# CO2_Sensor_SCD40.net
KiCad netlist of a schematic drawn in EAGLE
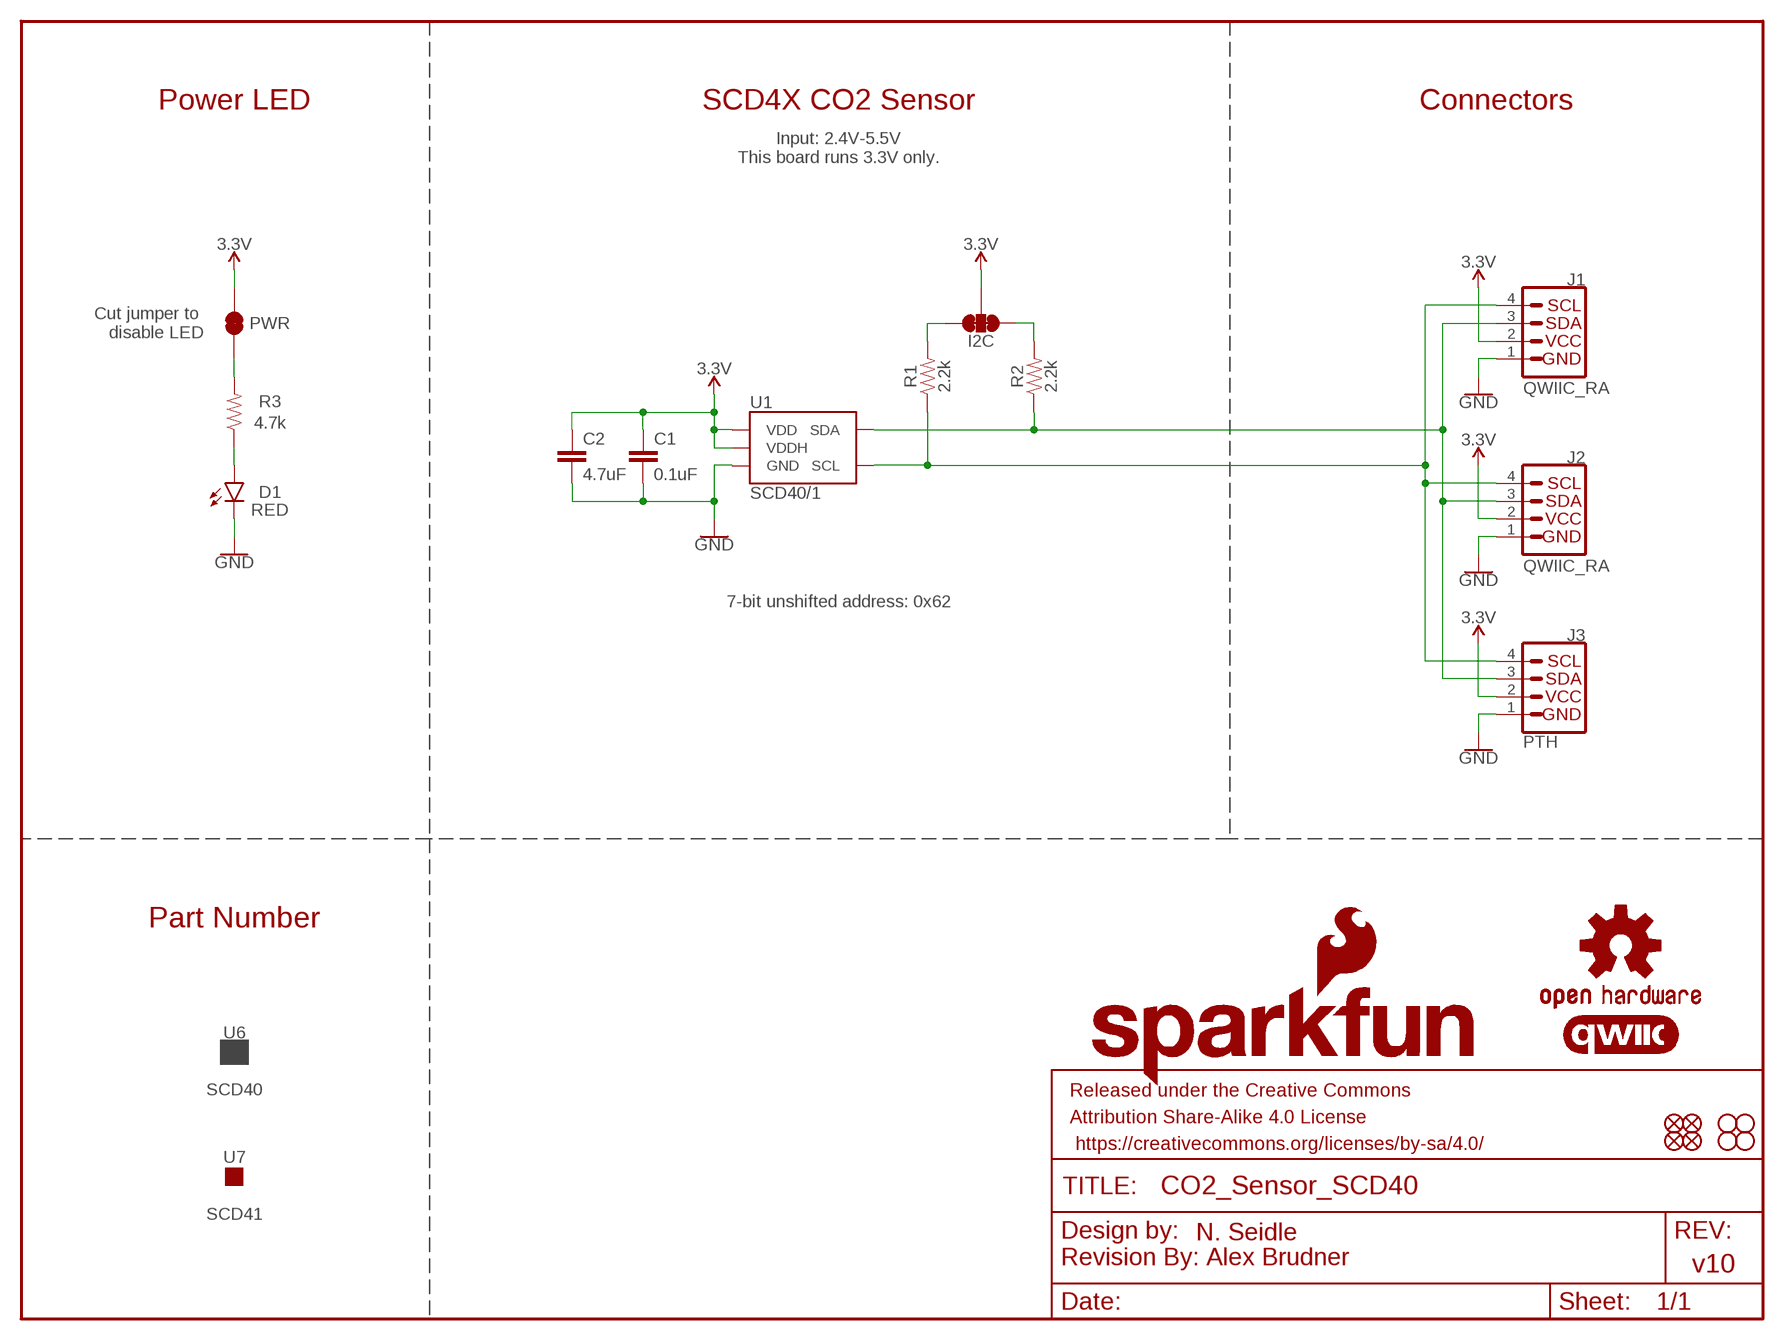
[diagram p0: schematic, sheet 1]

(export (version "E")
  (design (tool "Eeschema 10.0.6"))
  (components
    (comp (ref "C1")
      (value "0.1uF")
      (footprint "eagle-import:0603")
      (libsource (lib "eagle-import") (part "0.1UF-0603-25V-10%-X7R-WE"))
    )
    (comp (ref "C2")
      (value "4.7uF")
      (footprint "eagle-import:0603")
      (libsource (lib "eagle-import") (part "4.7UF-0603-6.3V-(10%)"))
    )
    (comp (ref "D1")
      (value "RED")
      (footprint "eagle-import:LED-0603")
      (libsource (lib "eagle-import") (part "LED-RED_0603-KB"))
    )
    (comp (ref "FD1")
      (value "FIDUCIALUFIDUCIAL")
      (footprint "eagle-import:FIDUCIAL-MICRO")
      (libsource (lib "eagle-import") (part "FIDUCIALUFIDUCIAL"))
    )
    (comp (ref "FD2")
      (value "FIDUCIALUFIDUCIAL")
      (footprint "eagle-import:FIDUCIAL-MICRO")
      (libsource (lib "eagle-import") (part "FIDUCIALUFIDUCIAL"))
    )
    (comp (ref "FD3")
      (value "FIDUCIALUFIDUCIAL")
      (footprint "eagle-import:FIDUCIAL-MICRO")
      (libsource (lib "eagle-import") (part "FIDUCIALUFIDUCIAL"))
    )
    (comp (ref "FD4")
      (value "FIDUCIALUFIDUCIAL")
      (footprint "eagle-import:FIDUCIAL-MICRO")
      (libsource (lib "eagle-import") (part "FIDUCIALUFIDUCIAL"))
    )
    (comp (ref "FRAME1")
      (value "FRAME-LETTER")
      (footprint "eagle-import:CREATIVE_COMMONS")
      (fields
        (field (name "BASEDON") "Revision By: Alex Brudner")
        (field (name "DESIGNER") "N. Seidle")
        (field (name "REV") "v10")
      )
      (libsource (lib "eagle-import") (part "FRAME-LETTER"))
    )
    (comp (ref "H1")
      (value "STAND-OFF")
      (footprint "eagle-import:STAND-OFF")
      (libsource (lib "eagle-import") (part "STAND-OFF"))
    )
    (comp (ref "H2")
      (value "STAND-OFF")
      (footprint "eagle-import:STAND-OFF")
      (libsource (lib "eagle-import") (part "STAND-OFF"))
    )
    (comp (ref "H3")
      (value "STAND-OFF")
      (footprint "eagle-import:STAND-OFF")
      (libsource (lib "eagle-import") (part "STAND-OFF"))
    )
    (comp (ref "H4")
      (value "STAND-OFF")
      (footprint "eagle-import:STAND-OFF")
      (libsource (lib "eagle-import") (part "STAND-OFF"))
    )
    (comp (ref "I2C")
      (value "I2C")
      (footprint "eagle-import:SMT-JUMPER_3_2-NC_TRACE_SILK")
      (libsource (lib "eagle-import") (part "JUMPER-SMT_3_2-NC_TRACE_SILK"))
    )
    (comp (ref "J1")
      (value "QWIIC_RA")
      (footprint "eagle-import:JST04_1MM_RA")
      (libsource (lib "eagle-import") (part "QWIIC_CONNECTORJS-1MM"))
    )
    (comp (ref "J2")
      (value "QWIIC_RA")
      (footprint "eagle-import:JST04_1MM_RA")
      (libsource (lib "eagle-import") (part "QWIIC_CONNECTORJS-1MM"))
    )
    (comp (ref "J3")
      (value "PTH")
      (footprint "eagle-import:1X04_NO_SILK")
      (libsource (lib "eagle-import") (part "I2C_STANDARD_NO_SILK"))
    )
    (comp (ref "LOGO1")
      (value "QWIIC_LOGO_CONNECTOR")
      (footprint "eagle-import:QWIIC_5.5MM")
      (libsource (lib "eagle-import") (part "QWIIC_LOGO_CONNECTOR"))
    )
    (comp (ref "LOGO2")
      (value "OSHW-LOGOS")
      (footprint "eagle-import:OSHW-LOGO-S")
      (libsource (lib "eagle-import") (part "OSHW-LOGOS"))
    )
    (comp (ref "LOGO3")
      (value "SFE_LOGO_NAME_FLAMEBLANK")
      (footprint "eagle-import:BLANK")
      (libsource (lib "eagle-import") (part "SFE_LOGO_NAME_FLAMEBLANK"))
    )
    (comp (ref "PWR")
      (value "PWR")
      (footprint "eagle-import:SMT-JUMPER_2_NC_TRACE_SILK")
      (libsource (lib "eagle-import") (part "JUMPER-SMT_2_NC_TRACE_SILK"))
    )
    (comp (ref "R1")
      (value "2.2k")
      (footprint "eagle-import:0603")
      (libsource (lib "eagle-import") (part "2.2KOHM-0603-1/10W-1%"))
    )
    (comp (ref "R2")
      (value "2.2k")
      (footprint "eagle-import:0603")
      (libsource (lib "eagle-import") (part "2.2KOHM-0603-1/10W-1%"))
    )
    (comp (ref "R3")
      (value "4.7k")
      (footprint "eagle-import:0603")
      (libsource (lib "eagle-import") (part "4.7KOHM-0603-1/10W-1%"))
    )
    (comp (ref "U1")
      (value "SCD40/1")
      (footprint "eagle-import:SCD4X")
      (libsource (lib "eagle-import") (part "SCD4X"))
    )
    (comp (ref "U6")
      (value "SCD40")
      (footprint "eagle-import:PRODUCT_IDENT_PASTE_NO-SILK")
      (libsource (lib "eagle-import") (part "PROD_ID_PASTE_NO-SILK"))
    )
    (comp (ref "U7")
      (value "SCD41")
      (footprint "eagle-import:PRODUCT_IDENT_NO_NO-SILK")
      (libsource (lib "eagle-import") (part "PROD_ID_NO-PASTE_NO_SILK"))
    )
  )
  (nets
    (net (code "1") (name "3.3V") (class "Default")
      (node (ref "C1") (pin "1") (pinfunction "1_1") (pintype "passive"))
      (node (ref "C2") (pin "1") (pinfunction "1_1") (pintype "passive"))
      (node (ref "I2C") (pin "2") (pinfunction "2_2") (pintype "passive"))
      (node (ref "J1") (pin "2") (pinfunction "2_2") (pintype "power_in"))
      (node (ref "J2") (pin "2") (pinfunction "2_2") (pintype "power_in"))
      (node (ref "J3") (pin "2") (pinfunction "2_2") (pintype "power_in"))
      (node (ref "PWR") (pin "2") (pinfunction "2_2") (pintype "passive"))
      (node (ref "U1") (pin "19") (pinfunction "VDDH_19") (pintype "power_in"))
      (node (ref "U1") (pin "7") (pinfunction "VDD_7") (pintype "power_in"))
    )
    (net (code "2") (name "GND") (class "Default")
      (node (ref "C1") (pin "2") (pinfunction "2_2") (pintype "passive"))
      (node (ref "C2") (pin "2") (pinfunction "2_2") (pintype "passive"))
      (node (ref "D1") (pin "C") (pinfunction "C_C") (pintype "passive"))
      (node (ref "J1") (pin "1") (pinfunction "1_1") (pintype "power_in"))
      (node (ref "J2") (pin "1") (pinfunction "1_1") (pintype "power_in"))
      (node (ref "J3") (pin "1") (pinfunction "1_1") (pintype "power_in"))
      (node (ref "U1") (pin "20") (pinfunction "GND_20") (pintype "power_in"))
      (node (ref "U1") (pin "6") (pinfunction "GND_6") (pintype "power_in"))
      (node (ref "U1") (pin "CP") (pinfunction "GND_CP") (pintype "power_in"))
    )
    (net (code "3") (name "Net-(D1-PadA)") (class "Default")
      (node (ref "D1") (pin "A") (pinfunction "A_A") (pintype "passive"))
      (node (ref "R3") (pin "1") (pinfunction "1_1") (pintype "passive"))
    )
    (net (code "4") (name "Net-(I2C-Pad1)") (class "Default")
      (node (ref "I2C") (pin "1") (pinfunction "1_1") (pintype "passive"))
      (node (ref "R2") (pin "2") (pinfunction "2_2") (pintype "passive"))
    )
    (net (code "5") (name "Net-(I2C-Pad3)") (class "Default")
      (node (ref "I2C") (pin "3") (pinfunction "3_3") (pintype "passive"))
      (node (ref "R1") (pin "2") (pinfunction "2_2") (pintype "passive"))
    )
    (net (code "6") (name "Net-(PWR-Pad1)") (class "Default")
      (node (ref "PWR") (pin "1") (pinfunction "1_1") (pintype "passive"))
      (node (ref "R3") (pin "2") (pinfunction "2_2") (pintype "passive"))
    )
    (net (code "7") (name "Net-(U1-SCL)") (class "Default")
      (node (ref "J1") (pin "4") (pinfunction "4_4") (pintype "passive"))
      (node (ref "J2") (pin "4") (pinfunction "4_4") (pintype "passive"))
      (node (ref "J3") (pin "4") (pinfunction "4_4") (pintype "passive"))
      (node (ref "R1") (pin "1") (pinfunction "1_1") (pintype "passive"))
      (node (ref "U1") (pin "9") (pinfunction "SCL_9") (pintype "bidirectional"))
    )
    (net (code "8") (name "Net-(U1-SDA)") (class "Default")
      (node (ref "J1") (pin "3") (pinfunction "3_3") (pintype "passive"))
      (node (ref "J2") (pin "3") (pinfunction "3_3") (pintype "passive"))
      (node (ref "J3") (pin "3") (pinfunction "3_3") (pintype "passive"))
      (node (ref "R2") (pin "1") (pinfunction "1_1") (pintype "passive"))
      (node (ref "U1") (pin "10") (pinfunction "SDA_10") (pintype "bidirectional"))
    )
  )
)
